# Thermometer.net
KiCad netlist of a schematic drawn in Altium Designer
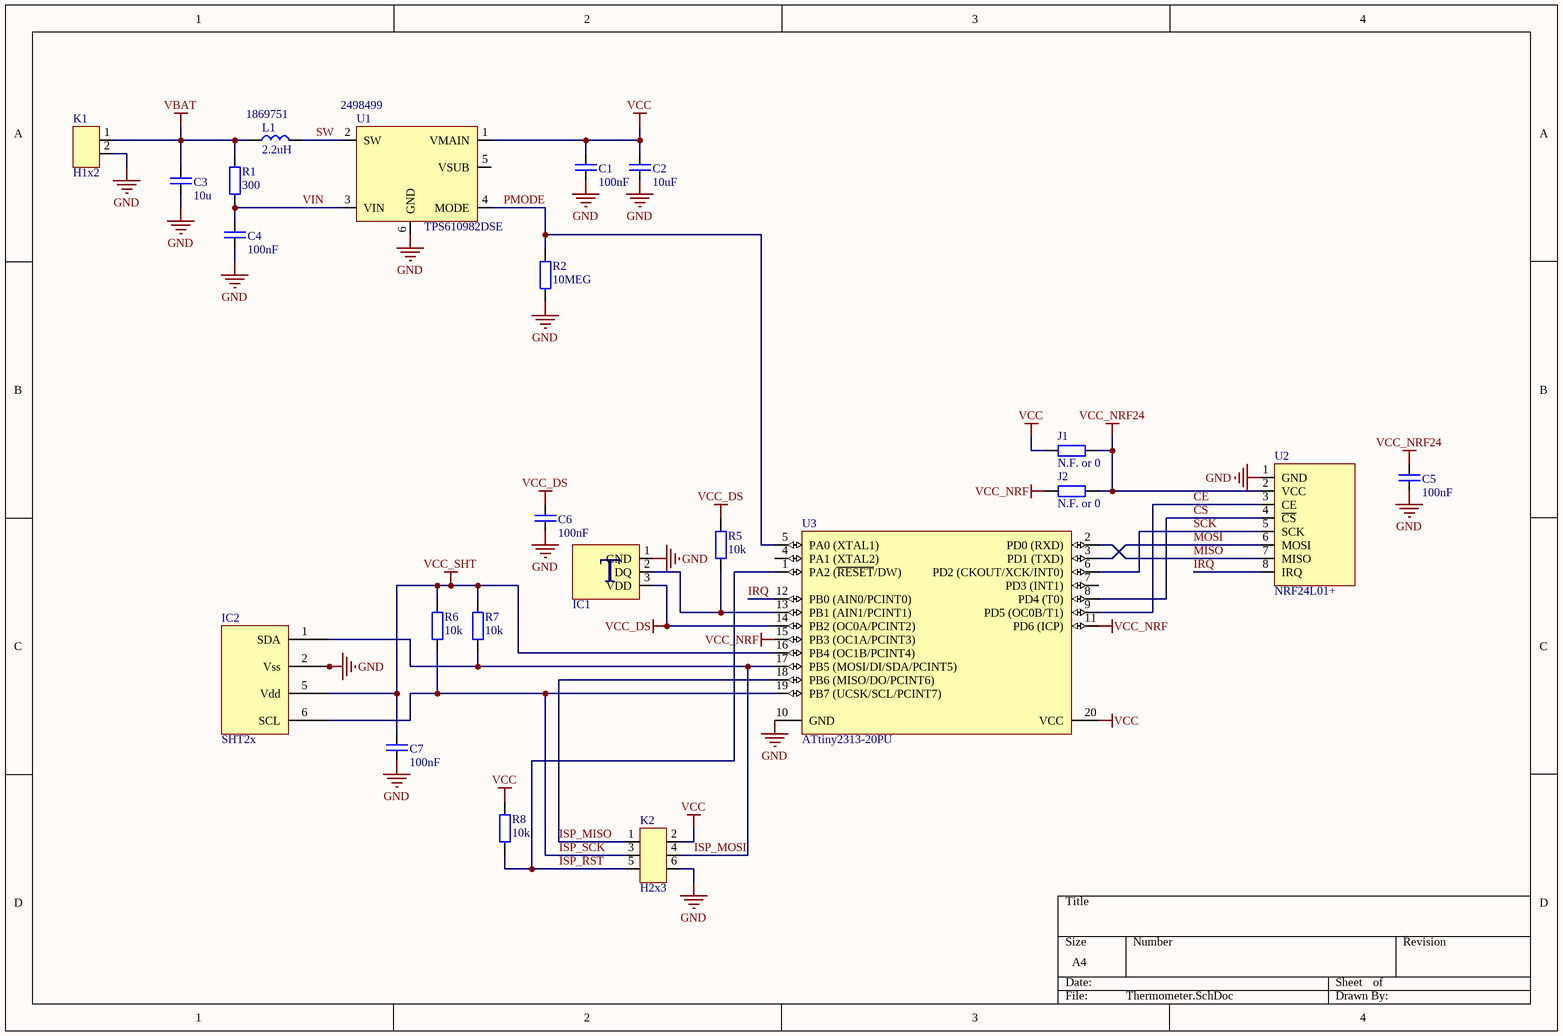
[diagram p0: Thermometer.SchDoc]

(export (version "E")
  (design (tool "Eeschema 10.0.6"))
  (components
    (comp (ref "C1")
      (value "100nF")
      (footprint "C2012_0805I_M")
      (description "Capacitor")
      (libsource (lib "General") (part "C"))
    )
    (comp (ref "C2")
      (value "10uF")
      (footprint "C3225_1210I_M")
      (description "Capacitor")
      (libsource (lib "General") (part "C"))
    )
    (comp (ref "C3")
      (value "10u")
      (footprint "C3225_1210I_M")
      (description "Capacitor")
      (libsource (lib "General") (part "C"))
    )
    (comp (ref "C4")
      (value "100nF")
      (footprint "C2012_0805I_M")
      (description "Capacitor")
      (libsource (lib "General") (part "C"))
    )
    (comp (ref "C5")
      (value "100nF")
      (footprint "C2012_0805I_M")
      (description "Capacitor")
      (libsource (lib "General") (part "C"))
    )
    (comp (ref "C6")
      (value "100nF")
      (footprint "C2012_0805I_M")
      (description "Capacitor")
      (libsource (lib "General") (part "C"))
    )
    (comp (ref "C7")
      (value "100nF")
      (footprint "C2012_0805I_M")
      (description "Capacitor")
      (libsource (lib "General") (part "C"))
    )
    (comp (ref "IC1")
      (value "DS18B20")
      (footprint "TO92")
      (description "Temperature sensor 1-wire interface")
      (libsource (lib "ICgeneral") (part "DS18B20"))
    )
    (comp (ref "IC2")
      (value "SHT2x")
      (footprint "DFN6")
      (fields (field (name "VOLTAGE") "50V") (field (name "TOLERANCE") "5%"))
      (libsource (lib "ICgeneral") (part "SHT2x"))
    )
    (comp (ref "J1")
      (value "N.F. or 0")
      (footprint "R2012_0805I_M")
      (description "R")
      (libsource (lib "General") (part "R"))
    )
    (comp (ref "J2")
      (value "N.F. or 0")
      (footprint "R2012_0805I_M")
      (description "R")
      (libsource (lib "General") (part "R"))
    )
    (comp (ref "K1")
      (value "H1x2")
      (footprint "H1x2")
      (description "Header 1x2 (male)")
      (libsource (lib "Kon_Tipk") (part "H1x2"))
    )
    (comp (ref "K2")
      (value "H2x3")
      (footprint "H2x3")
      (description "Header 2x3 (male)")
      (libsource (lib "Kon_Tipk") (part "H2x3"))
    )
    (comp (ref "L1")
      (value "2.2uH")
      (footprint "R2012_0805I_M")
      (description "L")
      (fields (field (name "SUPPLIER PART NUMBER 1") "1869751"))
      (libsource (lib "General") (part "L"))
    )
    (comp (ref "R1")
      (value "300")
      (footprint "R2012_0805I_M")
      (description "R")
      (libsource (lib "General") (part "R"))
    )
    (comp (ref "R2")
      (value "10MEG")
      (footprint "R2012_0805I_M")
      (description "R")
      (libsource (lib "General") (part "R"))
    )
    (comp (ref "R5")
      (value "10k")
      (footprint "R2012_0805I_M")
      (description "R")
      (libsource (lib "General") (part "R"))
    )
    (comp (ref "R6")
      (value "10k")
      (footprint "R2012_0805I_M")
      (description "R")
      (libsource (lib "General") (part "R"))
    )
    (comp (ref "R7")
      (value "10k")
      (footprint "R2012_0805I_M")
      (description "R")
      (libsource (lib "General") (part "R"))
    )
    (comp (ref "R8")
      (value "10k")
      (footprint "R2012_0805I_M")
      (description "R")
      (libsource (lib "General") (part "R"))
    )
    (comp (ref "U1")
      (value "TPS610982DSE")
      (footprint "WSON6M")
      (fields (field (name "SUPPLIER PART NUMBER 1") "2498499"))
      (libsource (lib "ICgeneral") (part "TPS610982DSE"))
    )
    (comp (ref "U2")
      (value "NRF24L01+")
      (footprint "NRF24L01+tht_module")
      (description "2.4GHz low power, long range module")
      (libsource (lib "Modules") (part "NRF24L01+"))
    )
    (comp (ref "U3")
      (value "ATtiny2313-20PU")
      (footprint "20P3")
      (libsource (lib "Atmel Microcontroller tinyAVR") (part "ATtiny2313-20PU"))
    )
  )
  (nets
    (net (code "1") (name "/CE") (class "Default")
      (node (ref "U2") (pin "3") (pinfunction "CE_3") (pintype "passive"))
      (node (ref "U3") (pin "9") (pinfunction "PD5_(OC0B/T1)_9") (pintype "bidirectional"))
    )
    (net (code "2") (name "/CS") (class "Default")
      (node (ref "U2") (pin "4") (pinfunction "~{CS}_4") (pintype "passive"))
      (node (ref "U3") (pin "8") (pinfunction "PD4_(T0)_8") (pintype "bidirectional"))
    )
    (net (code "3") (name "/IRQ") (class "Default")
      (node (ref "U2") (pin "8") (pinfunction "IRQ_8") (pintype "passive"))
      (node (ref "U3") (pin "12") (pinfunction "PB0_(AIN0/PCINT0)_12") (pintype "bidirectional"))
    )
    (net (code "4") (name "/ISP_MISO") (class "Default")
      (node (ref "K2") (pin "1") (pinfunction "1_1") (pintype "passive"))
      (node (ref "U3") (pin "18") (pinfunction "PB6_(MISO/DO/PCINT6)_18") (pintype "bidirectional"))
    )
    (net (code "5") (name "/ISP_MOSI") (class "Default")
      (node (ref "IC2") (pin "1") (pinfunction "SDA_1") (pintype "open_collector"))
      (node (ref "K2") (pin "4") (pinfunction "4_4") (pintype "passive"))
      (node (ref "R7") (pin "2") (pintype "passive"))
      (node (ref "U3") (pin "17") (pinfunction "PB5_(MOSI/DI/SDA/PCINT5)_17") (pintype "bidirectional"))
    )
    (net (code "6") (name "/ISP_RST") (class "Default")
      (node (ref "K2") (pin "5") (pinfunction "5_5") (pintype "passive"))
      (node (ref "R8") (pin "2") (pintype "passive"))
      (node (ref "U3") (pin "1") (pinfunction "PA2_(~{RESET}/DW)_1") (pintype "bidirectional"))
    )
    (net (code "7") (name "/ISP_SCK") (class "Default")
      (node (ref "IC2") (pin "6") (pinfunction "SCL_6") (pintype "open_collector"))
      (node (ref "K2") (pin "3") (pinfunction "3_3") (pintype "passive"))
      (node (ref "R6") (pin "2") (pintype "passive"))
      (node (ref "U3") (pin "19") (pinfunction "PB7_(UCSK/SCL/PCINT7)_19") (pintype "bidirectional"))
    )
    (net (code "8") (name "/MISO") (class "Default")
      (node (ref "U2") (pin "7") (pinfunction "MISO_7") (pintype "passive"))
      (node (ref "U3") (pin "2") (pinfunction "PD0_(RXD)_2") (pintype "bidirectional"))
    )
    (net (code "9") (name "/MOSI") (class "Default")
      (node (ref "U2") (pin "6") (pinfunction "MOSI_6") (pintype "passive"))
      (node (ref "U3") (pin "3") (pinfunction "PD1_(TXD)_3") (pintype "bidirectional"))
    )
    (net (code "10") (name "/PMODE") (class "Default")
      (node (ref "R2") (pin "1") (pintype "passive"))
      (node (ref "U1") (pin "4") (pinfunction "MODE_4") (pintype "passive"))
      (node (ref "U3") (pin "5") (pinfunction "PA0_(XTAL1)_5") (pintype "bidirectional"))
    )
    (net (code "11") (name "/SCK") (class "Default")
      (node (ref "U2") (pin "5") (pinfunction "SCK_5") (pintype "passive"))
      (node (ref "U3") (pin "6") (pinfunction "PD2_(CKOUT/XCK/INT0)_6") (pintype "bidirectional"))
    )
    (net (code "12") (name "/SW") (class "Default")
      (node (ref "L1") (pin "2") (pintype "passive"))
      (node (ref "U1") (pin "2") (pinfunction "SW_2") (pintype "passive"))
    )
    (net (code "13") (name "/VIN") (class "Default")
      (node (ref "C4") (pin "1") (pinfunction "1_1") (pintype "passive"))
      (node (ref "R1") (pin "2") (pintype "passive"))
      (node (ref "U1") (pin "3") (pinfunction "VIN_3") (pintype "passive"))
    )
    (net (code "14") (name "GND") (class "Default")
      (node (ref "C1") (pin "2") (pinfunction "2_2") (pintype "passive"))
      (node (ref "C2") (pin "2") (pinfunction "2_2") (pintype "passive"))
      (node (ref "C3") (pin "2") (pinfunction "2_2") (pintype "passive"))
      (node (ref "C4") (pin "2") (pinfunction "2_2") (pintype "passive"))
      (node (ref "C5") (pin "2") (pinfunction "2_2") (pintype "passive"))
      (node (ref "C6") (pin "2") (pinfunction "2_2") (pintype "passive"))
      (node (ref "C7") (pin "2") (pinfunction "2_2") (pintype "passive"))
      (node (ref "IC1") (pin "1") (pinfunction "GND_1") (pintype "passive"))
      (node (ref "IC2") (pin "0") (pinfunction "power_pad_0") (pintype "power_in"))
      (node (ref "IC2") (pin "2") (pinfunction "Vss_2") (pintype "power_in"))
      (node (ref "K1") (pin "2") (pinfunction "2_2") (pintype "passive"))
      (node (ref "K2") (pin "6") (pinfunction "6_6") (pintype "passive"))
      (node (ref "R2") (pin "2") (pintype "passive"))
      (node (ref "U1") (pin "6") (pinfunction "GND_6") (pintype "passive"))
      (node (ref "U2") (pin "1") (pinfunction "GND_1") (pintype "passive"))
      (node (ref "U3") (pin "10") (pinfunction "GND_10") (pintype "power_in"))
    )
    (net (code "15") (name "Net-(IC1-DQ)") (class "Default")
      (node (ref "IC1") (pin "2") (pinfunction "DQ_2") (pintype "passive"))
      (node (ref "R5") (pin "2") (pintype "passive"))
      (node (ref "U3") (pin "13") (pinfunction "PB1_(AIN1/PCINT1)_13") (pintype "bidirectional"))
    )
    (net (code "16") (name "VBAT") (class "Default")
      (node (ref "C3") (pin "1") (pinfunction "1_1") (pintype "passive"))
      (node (ref "K1") (pin "1") (pinfunction "1_1") (pintype "passive"))
      (node (ref "L1") (pin "1") (pintype "passive"))
      (node (ref "R1") (pin "1") (pintype "passive"))
    )
    (net (code "17") (name "VCC") (class "Default")
      (node (ref "C1") (pin "1") (pinfunction "1_1") (pintype "passive"))
      (node (ref "C2") (pin "1") (pinfunction "1_1") (pintype "passive"))
      (node (ref "J1") (pin "1") (pintype "passive"))
      (node (ref "K2") (pin "2") (pinfunction "2_2") (pintype "passive"))
      (node (ref "R8") (pin "1") (pintype "passive"))
      (node (ref "U1") (pin "1") (pinfunction "VMAIN_1") (pintype "passive"))
      (node (ref "U3") (pin "20") (pinfunction "VCC_20") (pintype "power_in"))
    )
    (net (code "18") (name "VCC_DS") (class "Default")
      (node (ref "C6") (pin "1") (pinfunction "1_1") (pintype "passive"))
      (node (ref "IC1") (pin "3") (pinfunction "VDD_3") (pintype "passive"))
      (node (ref "R5") (pin "1") (pintype "passive"))
      (node (ref "U3") (pin "14") (pinfunction "PB2_(OC0A/PCINT2)_14") (pintype "bidirectional"))
    )
    (net (code "19") (name "VCC_NRF") (class "Default")
      (node (ref "J2") (pin "1") (pintype "passive"))
      (node (ref "U3") (pin "11") (pinfunction "PD6_(ICP)_11") (pintype "bidirectional"))
      (node (ref "U3") (pin "15") (pinfunction "PB3_(OC1A/PCINT3)_15") (pintype "bidirectional"))
    )
    (net (code "20") (name "VCC_NRF24") (class "Default")
      (node (ref "C5") (pin "1") (pinfunction "1_1") (pintype "passive"))
      (node (ref "J1") (pin "2") (pintype "passive"))
      (node (ref "J2") (pin "2") (pintype "passive"))
      (node (ref "U2") (pin "2") (pinfunction "VCC_2") (pintype "passive"))
    )
    (net (code "21") (name "VCC_SHT") (class "Default")
      (node (ref "C7") (pin "1") (pinfunction "1_1") (pintype "passive"))
      (node (ref "IC2") (pin "5") (pinfunction "Vdd_5") (pintype "power_in"))
      (node (ref "R6") (pin "1") (pintype "passive"))
      (node (ref "R7") (pin "1") (pintype "passive"))
      (node (ref "U3") (pin "16") (pinfunction "PB4_(OC1B/PCINT4)_16") (pintype "bidirectional"))
    )
    (net (code "22") (name "unconnected-(U1-VSUB-Pad5)") (class "Default")
      (node (ref "U1") (pin "5") (pinfunction "VSUB_5") (pintype "passive"))
    )
    (net (code "23") (name "unconnected-(U3-PA1_(XTAL2)-Pad4)") (class "Default")
      (node (ref "U3") (pin "4") (pinfunction "PA1_(XTAL2)_4") (pintype "bidirectional"))
    )
    (net (code "24") (name "unconnected-(U3-PD3_(INT1)-Pad7)") (class "Default")
      (node (ref "U3") (pin "7") (pinfunction "PD3_(INT1)_7") (pintype "bidirectional"))
    )
  )
)
